# I2C_PowerMonitor_INA226.net
KiCad netlist of a schematic drawn in Altium Designer
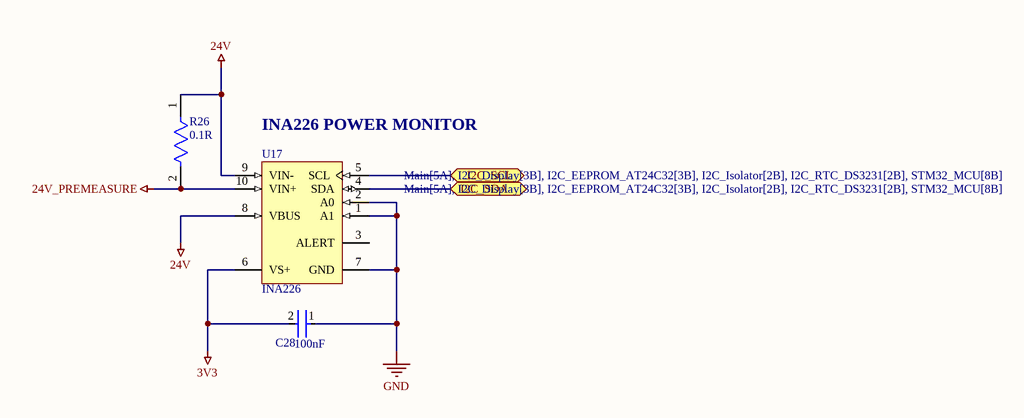
[diagram p0: I2C_PowerMonitor_INA226.SchDoc]

(export (version "E")
  (design (tool "Eeschema 10.0.6"))
  (components
    (comp (ref "C28")
      (value "100nF")
      (footprint "FP-CGA3E-0_3-0_1-IPC_A")
      (description "Cap Ceramic 100nF 50V X7R 10% Pad SMD 0603 +125°C Automotive T/R")
      (fields (field (name "TOLERANCE") "10%") (field (name "VOLTAGE") "50V"))
      (libsource (lib "Altium Content Vault") (part "b4654b650e69147ec39a6b967a45e02"))
    )
    (comp (ref "R26")
      (value "0.1R")
      (footprint "FP-RMCF2512-IPC_B")
      (description "0.1Ω ±5% 1W 2512 Thick Film Chip Resistor AEC-Q200 compliant")
      (fields (field (name "TOLERANCE") "5%"))
      (libsource (lib "Altium Content Vault") (part "1029c3af85768c4190bb7ad29bc67b5"))
    )
    (comp (ref "U17")
      (value "INA226")
      (footprint "DGS0010A_L")
      (fields (field (name "PARTNUMBER") "INA226AIDGSR"))
      (libsource (lib "Altium Content Vault") (part "TI-INA226DGS10"))
    )
  )
  (nets
    (net (code "1") (name "/I2C_SCL") (class "Default")
      (node (ref "U17") (pin "5") (pinfunction "SCL_5") (pintype "input"))
    )
    (net (code "2") (name "/I2C_SDA") (class "Default")
      (node (ref "U17") (pin "4") (pinfunction "SDA_4") (pintype "bidirectional"))
    )
    (net (code "3") (name "3V3") (class "Default")
      (node (ref "C28") (pin "2") (pinfunction "2_2") (pintype "passive"))
      (node (ref "U17") (pin "6") (pinfunction "VS+_6") (pintype "power_in"))
    )
    (net (code "4") (name "24V") (class "Default")
      (node (ref "R26") (pin "1") (pinfunction "1_1") (pintype "passive"))
      (node (ref "U17") (pin "8") (pinfunction "VBUS_8") (pintype "input"))
      (node (ref "U17") (pin "9") (pinfunction "VIN-_9") (pintype "input"))
    )
    (net (code "5") (name "24V_PREMEASURE") (class "Default")
      (node (ref "R26") (pin "2") (pinfunction "2_2") (pintype "passive"))
      (node (ref "U17") (pin "10") (pinfunction "VIN+_10") (pintype "input"))
    )
    (net (code "6") (name "GND") (class "Default")
      (node (ref "C28") (pin "1") (pinfunction "1_1") (pintype "passive"))
      (node (ref "U17") (pin "1") (pinfunction "A1_1") (pintype "input"))
      (node (ref "U17") (pin "2") (pinfunction "A0_2") (pintype "input"))
      (node (ref "U17") (pin "7") (pinfunction "GND_7") (pintype "power_in"))
    )
    (net (code "7") (name "unconnected-(U17-ALERT-Pad3)") (class "Default")
      (node (ref "U17") (pin "3") (pinfunction "ALERT_3") (pintype "open_collector"))
    )
  )
)
